# OptocouplerTest.net
KiCad netlist of a schematic drawn in EAGLE
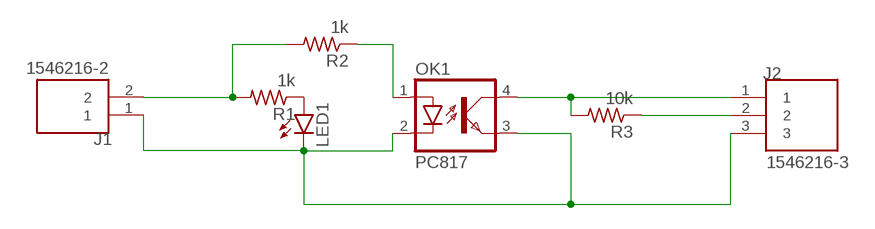
[diagram p0: schematic, sheet 1]

(export (version "E")
  (design (tool "Eeschema 10.0.6"))
  (components
    (comp (ref "J1")
      (value "1546216-2")
      (footprint "eagle-import:TE_1546216-2")
      (fields (field (name "MF") "TE Connectivity"))
      (libsource (lib "eagle-import") (part "1546216-2"))
    )
    (comp (ref "J2")
      (value "1546216-3")
      (footprint "eagle-import:TE_1546216-3")
      (fields (field (name "MF") "TE Connectivity"))
      (libsource (lib "eagle-import") (part "1546216-3"))
    )
    (comp (ref "LED1")
      (value "LED3MM")
      (footprint "eagle-import:LED3MM")
      (libsource (lib "eagle-import") (part "LED3MM"))
    )
    (comp (ref "OK1")
      (value "PC817")
      (footprint "eagle-import:DIL04")
      (fields (field (name "MPN") "PC817X4J000F"))
      (libsource (lib "eagle-import") (part "PC817"))
    )
    (comp (ref "R1")
      (value "1k")
      (footprint "eagle-import:0207_15")
      (libsource (lib "eagle-import") (part "R-US_0207/15"))
    )
    (comp (ref "R2")
      (value "1k")
      (footprint "eagle-import:0207_15")
      (libsource (lib "eagle-import") (part "R-US_0207/15"))
    )
    (comp (ref "R3")
      (value "10k")
      (footprint "eagle-import:0207_15")
      (libsource (lib "eagle-import") (part "R-US_0207/15"))
    )
  )
  (nets
    (net (code "1") (name "Net-(J1-Pad2)") (class "Default")
      (node (ref "J1") (pin "2") (pinfunction "2_2") (pintype "passive"))
      (node (ref "R1") (pin "2") (pinfunction "2_2") (pintype "passive"))
      (node (ref "R2") (pin "2") (pinfunction "2_2") (pintype "passive"))
    )
    (net (code "2") (name "Net-(J2-Pad2)") (class "Default")
      (node (ref "J2") (pin "2") (pinfunction "2_2") (pintype "passive"))
      (node (ref "R3") (pin "1") (pinfunction "1_1") (pintype "passive"))
    )
    (net (code "3") (name "Net-(LED1-C)") (class "Default")
      (node (ref "J1") (pin "1") (pinfunction "1_1") (pintype "passive"))
      (node (ref "J2") (pin "3") (pinfunction "3_3") (pintype "passive"))
      (node (ref "LED1") (pin "K") (pinfunction "C_K") (pintype "passive"))
      (node (ref "OK1") (pin "2") (pinfunction "C_2") (pintype "passive"))
      (node (ref "OK1") (pin "3") (pinfunction "EMIT_3") (pintype "passive"))
    )
    (net (code "4") (name "Net-(LED1-PadA)") (class "Default")
      (node (ref "LED1") (pin "A") (pinfunction "A_A") (pintype "passive"))
      (node (ref "R1") (pin "1") (pinfunction "1_1") (pintype "passive"))
    )
    (net (code "5") (name "Net-(OK1-A)") (class "Default")
      (node (ref "OK1") (pin "1") (pinfunction "A_1") (pintype "passive"))
      (node (ref "R2") (pin "1") (pinfunction "1_1") (pintype "passive"))
    )
    (net (code "6") (name "Net-(OK1-COL)") (class "Default")
      (node (ref "J2") (pin "1") (pinfunction "1_1") (pintype "passive"))
      (node (ref "OK1") (pin "4") (pinfunction "COL_4") (pintype "passive"))
      (node (ref "R3") (pin "2") (pinfunction "2_2") (pintype "passive"))
    )
  )
)
